# BannerTestSch.net
KiCad netlist of a schematic drawn in Altium Designer
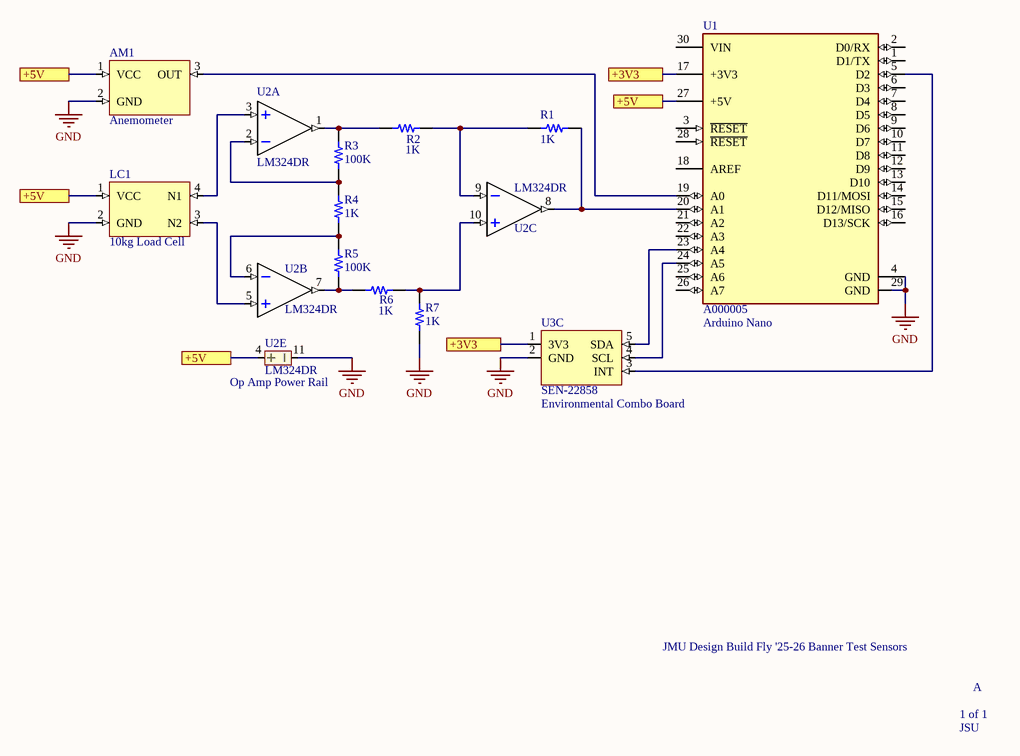
[diagram p0: BannerTestSch.SchDoc]

(export (version "E")
  (design (tool "Eeschema 10.0.6"))
  (components
    (comp (ref "AM1") (value "Anemometer") (libsource (lib "JoeyLib") (part "Anemometer")))
    (comp (ref "LC1")
      (value "10kg Load Cell")
      (description "10KG Strain Gauge Load Cell, 4 Wire, by Adafruit")
      (libsource (lib "JoeyLib") (part "4542 10kg Load Cell"))
    )
    (comp (ref "R1")
      (value "1K")
      (footprint "RESC1206(3216)_L")
      (description "RES 1.00K OHM 1/4W 1% 1206 SMD")
      (fields (field (name "TOLERANCE") "1%") (field (name "MFG") "PANASONIC"))
      (libsource (lib "ComSonicsResistors") (part "ERJ-8ENF1001V"))
    )
    (comp (ref "R2")
      (value "1K")
      (footprint "RESC1206(3216)_L")
      (description "RES 1.00K OHM 1/4W 1% 1206 SMD")
      (fields (field (name "TOLERANCE") "1%") (field (name "MFG") "PANASONIC"))
      (libsource (lib "ComSonicsResistors") (part "ERJ-8ENF1001V"))
    )
    (comp (ref "R3")
      (value "100K")
      (footprint "RESC0603(1608)_L")
      (description "RES 100K OHM 1/10W 5% 0603 SMD")
      (fields (field (name "MFG") "ROHM") (field (name "MFG_PART_NO") "MCR03EZPJ104"))
      (libsource (lib "ComSonicsResistors") (part "ERJ-3EKF1003V"))
    )
    (comp (ref "R4")
      (value "1K")
      (footprint "RESC1206(3216)_L")
      (description "RES 1.00K OHM 1/4W 1% 1206 SMD")
      (fields (field (name "TOLERANCE") "1%") (field (name "MFG") "PANASONIC"))
      (libsource (lib "ComSonicsResistors") (part "ERJ-8ENF1001V"))
    )
    (comp (ref "R5")
      (value "100K")
      (footprint "RESC0603(1608)_L")
      (description "RES 100K OHM 1/10W 5% 0603 SMD")
      (fields (field (name "MFG") "ROHM") (field (name "MFG_PART_NO") "MCR03EZPJ104"))
      (libsource (lib "ComSonicsResistors") (part "ERJ-3EKF1003V"))
    )
    (comp (ref "R6")
      (value "1K")
      (footprint "RESC1206(3216)_L")
      (description "RES 1.00K OHM 1/4W 1% 1206 SMD")
      (fields (field (name "TOLERANCE") "1%") (field (name "MFG") "PANASONIC"))
      (libsource (lib "ComSonicsResistors") (part "ERJ-8ENF1001V"))
    )
    (comp (ref "R7")
      (value "1K")
      (footprint "RESC1206(3216)_L")
      (description "RES 1.00K OHM 1/4W 1% 1206 SMD")
      (fields (field (name "TOLERANCE") "1%") (field (name "MFG") "PANASONIC"))
      (libsource (lib "ComSonicsResistors") (part "ERJ-8ENF1001V"))
    )
    (comp (ref "U1")
      (value "A000005")
      (footprint "FP-A000005-MFG")
      (description "ATmega328 Microcontroller Development Board 16MHz CPU 2KB RAM 1KB/32KB EEPROM/Flash")
      (libsource (lib "Comsonics, Inc") (part "d190c066e99afd1c6882cf92e11b2cc"))
    )
    (comp (ref "U2")
      (value "LM324DR")
      (footprint "SOIC-14")
      (description "General Purpose Amplifier 4 Circuit  14-SOIC")
      (fields (field (name "MFG") "Texas Instruments"))
      (libsource (lib "ComSonicsICs") (part "LM324DR"))
    )
    (comp (ref "U3")
      (value "SEN-22858")
      (description "Sparkfun Environmental Combo Bre")
      (fields (field (name "MANUFACTURER") "SparkFun"))
      (libsource (lib "JoeyLib") (part "SEN-22858"))
    )
  )
  (nets
    (net (code "1") (name "/+3V3") (class "Default")
      (node (ref "U1") (pin "17") (pinfunction "+3V3_17") (pintype "power_in"))
      (node (ref "U3") (pin "1") (pinfunction "3V3_1") (pintype "power_in"))
    )
    (net (code "2") (name "/+5V") (class "Default")
      (node (ref "AM1") (pin "1") (pinfunction "VCC_1") (pintype "input"))
      (node (ref "LC1") (pin "1") (pinfunction "VCC_1") (pintype "input"))
      (node (ref "U1") (pin "27") (pinfunction "+5V_27") (pintype "power_in"))
      (node (ref "U2") (pin "4") (pinfunction "VCC_4") (pintype "power_in"))
    )
    (net (code "3") (name "GND") (class "Default")
      (node (ref "AM1") (pin "2") (pinfunction "GND_2") (pintype "input"))
      (node (ref "LC1") (pin "2") (pinfunction "GND_2") (pintype "input"))
      (node (ref "R7") (pin "2") (pinfunction "2_2") (pintype "passive"))
      (node (ref "U1") (pin "29") (pinfunction "GND_29") (pintype "power_in"))
      (node (ref "U1") (pin "4") (pinfunction "GND_4") (pintype "power_in"))
      (node (ref "U2") (pin "11") (pinfunction "GND_11") (pintype "power_in"))
      (node (ref "U3") (pin "2") (pinfunction "GND_2") (pintype "power_in"))
    )
    (net (code "4") (name "Net-(AM1-OUT)") (class "Default")
      (node (ref "AM1") (pin "3") (pinfunction "OUT_3") (pintype "input"))
      (node (ref "U1") (pin "19") (pinfunction "A0_19") (pintype "bidirectional"))
    )
    (net (code "5") (name "Net-(LC1-N1)") (class "Default")
      (node (ref "LC1") (pin "4") (pinfunction "N1_4") (pintype "input"))
      (node (ref "U2") (pin "3") (pinfunction "IN+1_3") (pintype "input"))
    )
    (net (code "6") (name "Net-(LC1-N2)") (class "Default")
      (node (ref "LC1") (pin "3") (pinfunction "N2_3") (pintype "input"))
      (node (ref "U2") (pin "5") (pinfunction "IN+2_5") (pintype "input"))
    )
    (net (code "7") (name "Net-(U1-A1)") (class "Default")
      (node (ref "R1") (pin "2") (pinfunction "2_2") (pintype "passive"))
      (node (ref "U1") (pin "20") (pinfunction "A1_20") (pintype "bidirectional"))
      (node (ref "U2") (pin "8") (pinfunction "OUT3_8") (pintype "output"))
    )
    (net (code "8") (name "Net-(U1-A4)") (class "Default")
      (node (ref "U1") (pin "23") (pinfunction "A4_23") (pintype "bidirectional"))
      (node (ref "U3") (pin "5") (pinfunction "SDA_5") (pintype "input"))
    )
    (net (code "9") (name "Net-(U1-A5)") (class "Default")
      (node (ref "U1") (pin "24") (pinfunction "A5_24") (pintype "bidirectional"))
      (node (ref "U3") (pin "4") (pinfunction "SCL_4") (pintype "input"))
    )
    (net (code "10") (name "Net-(U1-D2)") (class "Default")
      (node (ref "U1") (pin "5") (pinfunction "D2_5") (pintype "bidirectional"))
      (node (ref "U3") (pin "3") (pinfunction "INT_3") (pintype "input"))
    )
    (net (code "11") (name "Net-(U2A-IN-1)") (class "Default")
      (node (ref "R3") (pin "2") (pinfunction "2_2") (pintype "passive"))
      (node (ref "R4") (pin "1") (pinfunction "1_1") (pintype "passive"))
      (node (ref "U2") (pin "2") (pinfunction "IN-1_2") (pintype "input"))
    )
    (net (code "12") (name "Net-(U2A-OUT1)") (class "Default")
      (node (ref "R2") (pin "1") (pinfunction "1_1") (pintype "passive"))
      (node (ref "R3") (pin "1") (pinfunction "1_1") (pintype "passive"))
      (node (ref "U2") (pin "1") (pinfunction "OUT1_1") (pintype "output"))
    )
    (net (code "13") (name "Net-(U2B-IN-2)") (class "Default")
      (node (ref "R4") (pin "2") (pinfunction "2_2") (pintype "passive"))
      (node (ref "R5") (pin "1") (pinfunction "1_1") (pintype "passive"))
      (node (ref "U2") (pin "6") (pinfunction "IN-2_6") (pintype "input"))
    )
    (net (code "14") (name "Net-(U2B-OUT2)") (class "Default")
      (node (ref "R5") (pin "2") (pinfunction "2_2") (pintype "passive"))
      (node (ref "R6") (pin "1") (pinfunction "1_1") (pintype "passive"))
      (node (ref "U2") (pin "7") (pinfunction "OUT2_7") (pintype "output"))
    )
    (net (code "15") (name "Net-(U2C-IN+3)") (class "Default")
      (node (ref "R6") (pin "2") (pinfunction "2_2") (pintype "passive"))
      (node (ref "R7") (pin "1") (pinfunction "1_1") (pintype "passive"))
      (node (ref "U2") (pin "10") (pinfunction "IN+3_10") (pintype "input"))
    )
    (net (code "16") (name "Net-(U2C-IN-3)") (class "Default")
      (node (ref "R1") (pin "1") (pinfunction "1_1") (pintype "passive"))
      (node (ref "R2") (pin "2") (pinfunction "2_2") (pintype "passive"))
      (node (ref "U2") (pin "9") (pinfunction "IN-3_9") (pintype "input"))
    )
    (net (code "17") (name "unconnected-(U1-A2-Pad21)") (class "Default")
      (node (ref "U1") (pin "21") (pinfunction "A2_21") (pintype "bidirectional"))
    )
    (net (code "18") (name "unconnected-(U1-A3-Pad22)") (class "Default")
      (node (ref "U1") (pin "22") (pinfunction "A3_22") (pintype "bidirectional"))
    )
    (net (code "19") (name "unconnected-(U1-A6-Pad25)") (class "Default")
      (node (ref "U1") (pin "25") (pinfunction "A6_25") (pintype "bidirectional"))
    )
    (net (code "20") (name "unconnected-(U1-A7-Pad26)") (class "Default")
      (node (ref "U1") (pin "26") (pinfunction "A7_26") (pintype "bidirectional"))
    )
    (net (code "21") (name "unconnected-(U1-AREF-Pad18)") (class "Default")
      (node (ref "U1") (pin "18") (pinfunction "AREF_18") (pintype "passive"))
    )
    (net (code "22") (name "unconnected-(U1-D0{slash}RX-Pad2)") (class "Default")
      (node (ref "U1") (pin "2") (pinfunction "D0/RX_2") (pintype "bidirectional"))
    )
    (net (code "23") (name "unconnected-(U1-D1{slash}TX-Pad1)") (class "Default")
      (node (ref "U1") (pin "1") (pinfunction "D1/TX_1") (pintype "bidirectional"))
    )
    (net (code "24") (name "unconnected-(U1-D3-Pad6)") (class "Default")
      (node (ref "U1") (pin "6") (pinfunction "D3_6") (pintype "bidirectional"))
    )
    (net (code "25") (name "unconnected-(U1-D4-Pad7)") (class "Default")
      (node (ref "U1") (pin "7") (pinfunction "D4_7") (pintype "bidirectional"))
    )
    (net (code "26") (name "unconnected-(U1-D5-Pad8)") (class "Default")
      (node (ref "U1") (pin "8") (pinfunction "D5_8") (pintype "bidirectional"))
    )
    (net (code "27") (name "unconnected-(U1-D6-Pad9)") (class "Default")
      (node (ref "U1") (pin "9") (pinfunction "D6_9") (pintype "bidirectional"))
    )
    (net (code "28") (name "unconnected-(U1-D7-Pad10)") (class "Default")
      (node (ref "U1") (pin "10") (pinfunction "D7_10") (pintype "bidirectional"))
    )
    (net (code "29") (name "unconnected-(U1-D8-Pad11)") (class "Default")
      (node (ref "U1") (pin "11") (pinfunction "D8_11") (pintype "bidirectional"))
    )
    (net (code "30") (name "unconnected-(U1-D9-Pad12)") (class "Default")
      (node (ref "U1") (pin "12") (pinfunction "D9_12") (pintype "bidirectional"))
    )
    (net (code "31") (name "unconnected-(U1-D10-Pad13)") (class "Default")
      (node (ref "U1") (pin "13") (pinfunction "D10_13") (pintype "bidirectional"))
    )
    (net (code "32") (name "unconnected-(U1-D11{slash}MOSI-Pad14)") (class "Default")
      (node (ref "U1") (pin "14") (pinfunction "D11/MOSI_14") (pintype "bidirectional"))
    )
    (net (code "33") (name "unconnected-(U1-D12{slash}MISO-Pad15)") (class "Default")
      (node (ref "U1") (pin "15") (pinfunction "D12/MISO_15") (pintype "bidirectional"))
    )
    (net (code "34") (name "unconnected-(U1-D13{slash}SCK-Pad16)") (class "Default")
      (node (ref "U1") (pin "16") (pinfunction "D13/SCK_16") (pintype "bidirectional"))
    )
    (net (code "35") (name "unconnected-(U1-VIN-Pad30)") (class "Default")
      (node (ref "U1") (pin "30") (pinfunction "VIN_30") (pintype "power_in"))
    )
    (net (code "36") (name "unconnected-(U1-~{RESET}-Pad3)") (class "Default")
      (node (ref "U1") (pin "3") (pinfunction "~{RESET}_3") (pintype "input"))
    )
    (net (code "37") (name "unconnected-(U1-~{RESET}-Pad28)") (class "Default")
      (node (ref "U1") (pin "28") (pinfunction "~{RESET}_28") (pintype "input"))
    )
  )
)
